# LiPo_Booster_v1_2.net
KiCad netlist of a schematic drawn in EAGLE
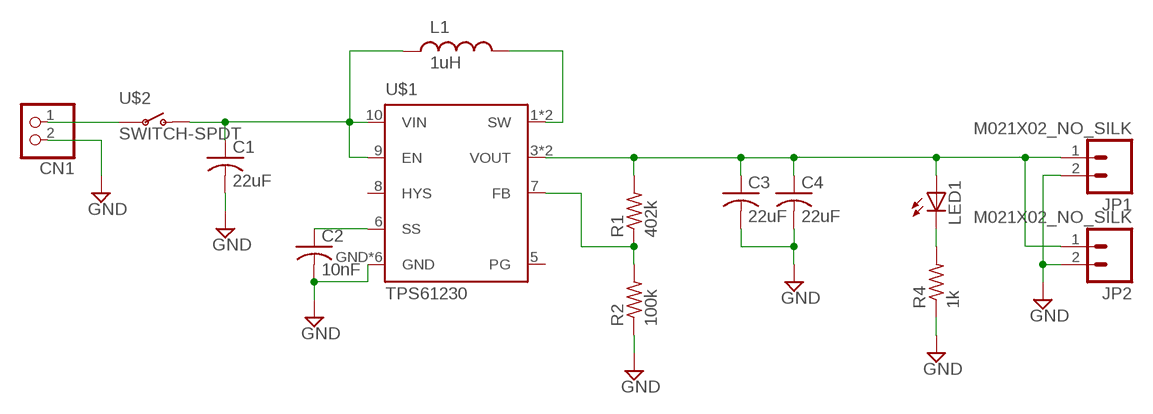
[diagram p0: schematic, sheet 1]

(export (version "E")
  (design (tool "Eeschema 10.0.6"))
  (components
    (comp (ref "C1")
      (value "22uF")
      (footprint "eagle-import:C0603K")
      (libsource (lib "eagle-import") (part "C-USC0603K"))
    )
    (comp (ref "C2")
      (value "10nF")
      (footprint "eagle-import:C0603K")
      (libsource (lib "eagle-import") (part "C-USC0603K"))
    )
    (comp (ref "C3")
      (value "22uF")
      (footprint "eagle-import:C0603K")
      (libsource (lib "eagle-import") (part "C-USC0603K"))
    )
    (comp (ref "C4")
      (value "22uF")
      (footprint "eagle-import:C0603K")
      (libsource (lib "eagle-import") (part "C-USC0603K"))
    )
    (comp (ref "CN1")
      (value "JST_2PIN-SMT-RA")
      (footprint "eagle-import:JST-PH-2-SMT-RA")
      (libsource (lib "eagle-import") (part "JST_2PIN-SMT-RA"))
    )
    (comp (ref "JP1")
      (value "M021X02_NO_SILK")
      (footprint "eagle-import:1X02_NO_SILK")
      (libsource (lib "eagle-import") (part "M021X02_NO_SILK"))
    )
    (comp (ref "JP2")
      (value "M021X02_NO_SILK")
      (footprint "eagle-import:1X02_NO_SILK")
      (libsource (lib "eagle-import") (part "M021X02_NO_SILK"))
    )
    (comp (ref "L1")
      (value "1uH")
      (footprint "eagle-import:XFL4020")
      (libsource (lib "eagle-import") (part "XFL4020"))
    )
    (comp (ref "LED1")
      (value "LEDCHIPLED_0603")
      (footprint "eagle-import:CHIPLED_0603")
      (libsource (lib "eagle-import") (part "LEDCHIPLED_0603"))
    )
    (comp (ref "R1")
      (value "402k")
      (footprint "eagle-import:R0603")
      (libsource (lib "eagle-import") (part "R-US_R0603"))
    )
    (comp (ref "R2")
      (value "100k")
      (footprint "eagle-import:R0603")
      (libsource (lib "eagle-import") (part "R-US_R0603"))
    )
    (comp (ref "R4")
      (value "1k")
      (footprint "eagle-import:R0603")
      (libsource (lib "eagle-import") (part "R-US_R0603"))
    )
    (comp (ref "U$1")
      (value "TPS61230")
      (footprint "eagle-import:DRC-S-PVSON-N11")
      (libsource (lib "eagle-import") (part "TPS61230"))
    )
    (comp (ref "U$2")
      (value "SWITCH-SPDT")
      (footprint "eagle-import:JS102011")
      (libsource (lib "eagle-import") (part "SWITCH-SPDT"))
    )
  )
  (nets
    (net (code "1") (name "/PG") (class "Default")
      (node (ref "U$1") (pin "5") (pinfunction "PG_5") (pintype "power_in"))
    )
    (net (code "2") (name "GND") (class "Default")
      (node (ref "C1") (pin "2") (pinfunction "2_2") (pintype "passive"))
      (node (ref "C2") (pin "2") (pinfunction "2_2") (pintype "passive"))
      (node (ref "C3") (pin "2") (pinfunction "2_2") (pintype "passive"))
      (node (ref "C4") (pin "2") (pinfunction "2_2") (pintype "passive"))
      (node (ref "CN1") (pin "2") (pinfunction "1_2") (pintype "passive"))
      (node (ref "JP1") (pin "2") (pinfunction "2_2") (pintype "passive"))
      (node (ref "JP2") (pin "2") (pinfunction "2_2") (pintype "passive"))
      (node (ref "R2") (pin "1") (pinfunction "1_1") (pintype "passive"))
      (node (ref "R4") (pin "1") (pinfunction "1_1") (pintype "passive"))
      (node (ref "U$1") (pin "GND") (pinfunction "GND_GND") (pintype "power_in"))
      (node (ref "U$1") (pin "GND@1") (pinfunction "GND_GND@1") (pintype "power_in"))
      (node (ref "U$1") (pin "GND@2") (pinfunction "GND_GND@2") (pintype "power_in"))
      (node (ref "U$1") (pin "GND@3") (pinfunction "GND_GND@3") (pintype "power_in"))
      (node (ref "U$1") (pin "GND@4") (pinfunction "GND_GND@4") (pintype "power_in"))
      (node (ref "U$1") (pin "GND@5") (pinfunction "GND_GND@5") (pintype "power_in"))
    )
    (net (code "3") (name "Net-(C3-Pad1)") (class "Default")
      (node (ref "C3") (pin "1") (pinfunction "1_1") (pintype "passive"))
      (node (ref "C4") (pin "1") (pinfunction "1_1") (pintype "passive"))
      (node (ref "JP1") (pin "1") (pinfunction "1_1") (pintype "passive"))
      (node (ref "JP2") (pin "1") (pinfunction "1_1") (pintype "passive"))
      (node (ref "LED1") (pin "A") (pinfunction "A_A") (pintype "passive"))
      (node (ref "R1") (pin "2") (pinfunction "2_2") (pintype "passive"))
      (node (ref "U$1") (pin "3") (pinfunction "VOUT_3") (pintype "passive"))
      (node (ref "U$1") (pin "4") (pinfunction "VOUT_4") (pintype "passive"))
    )
    (net (code "4") (name "Net-(CN1-2)") (class "Default")
      (node (ref "CN1") (pin "1") (pinfunction "2_1") (pintype "passive"))
      (node (ref "U$2") (pin "P$3") (pinfunction "P_P$3") (pintype "passive"))
    )
    (net (code "5") (name "Net-(L1-1)") (class "Default")
      (node (ref "C1") (pin "1") (pinfunction "1_1") (pintype "passive"))
      (node (ref "L1") (pin "P$1") (pinfunction "1_P$1") (pintype "passive"))
      (node (ref "U$1") (pin "10") (pinfunction "VIN_10") (pintype "input"))
      (node (ref "U$1") (pin "9") (pinfunction "EN_9") (pintype "input"))
      (node (ref "U$2") (pin "P$2") (pinfunction "O_P$2") (pintype "passive"))
    )
    (net (code "6") (name "Net-(L1-2)") (class "Default")
      (node (ref "L1") (pin "P$2") (pinfunction "2_P$2") (pintype "passive"))
      (node (ref "U$1") (pin "1") (pinfunction "SW_1") (pintype "input"))
      (node (ref "U$1") (pin "2") (pinfunction "SW_2") (pintype "input"))
    )
    (net (code "7") (name "Net-(LED1-PadC)") (class "Default")
      (node (ref "LED1") (pin "C") (pinfunction "C_C") (pintype "passive"))
      (node (ref "R4") (pin "2") (pinfunction "2_2") (pintype "passive"))
    )
    (net (code "8") (name "Net-(U$1-FB)") (class "Default")
      (node (ref "R1") (pin "1") (pinfunction "1_1") (pintype "passive"))
      (node (ref "R2") (pin "2") (pinfunction "2_2") (pintype "passive"))
      (node (ref "U$1") (pin "7") (pinfunction "FB_7") (pintype "input"))
    )
    (net (code "9") (name "Net-(U$1-SS)") (class "Default")
      (node (ref "C2") (pin "1") (pinfunction "1_1") (pintype "passive"))
      (node (ref "U$1") (pin "6") (pinfunction "SS_6") (pintype "input"))
    )
    (net (code "10") (name "unconnected-(U$1-HYS-Pad8)") (class "Default")
      (node (ref "U$1") (pin "8") (pinfunction "HYS_8") (pintype "input"))
    )
  )
)
